# schematic.net
KiCad netlist of a schematic drawn in EAGLE
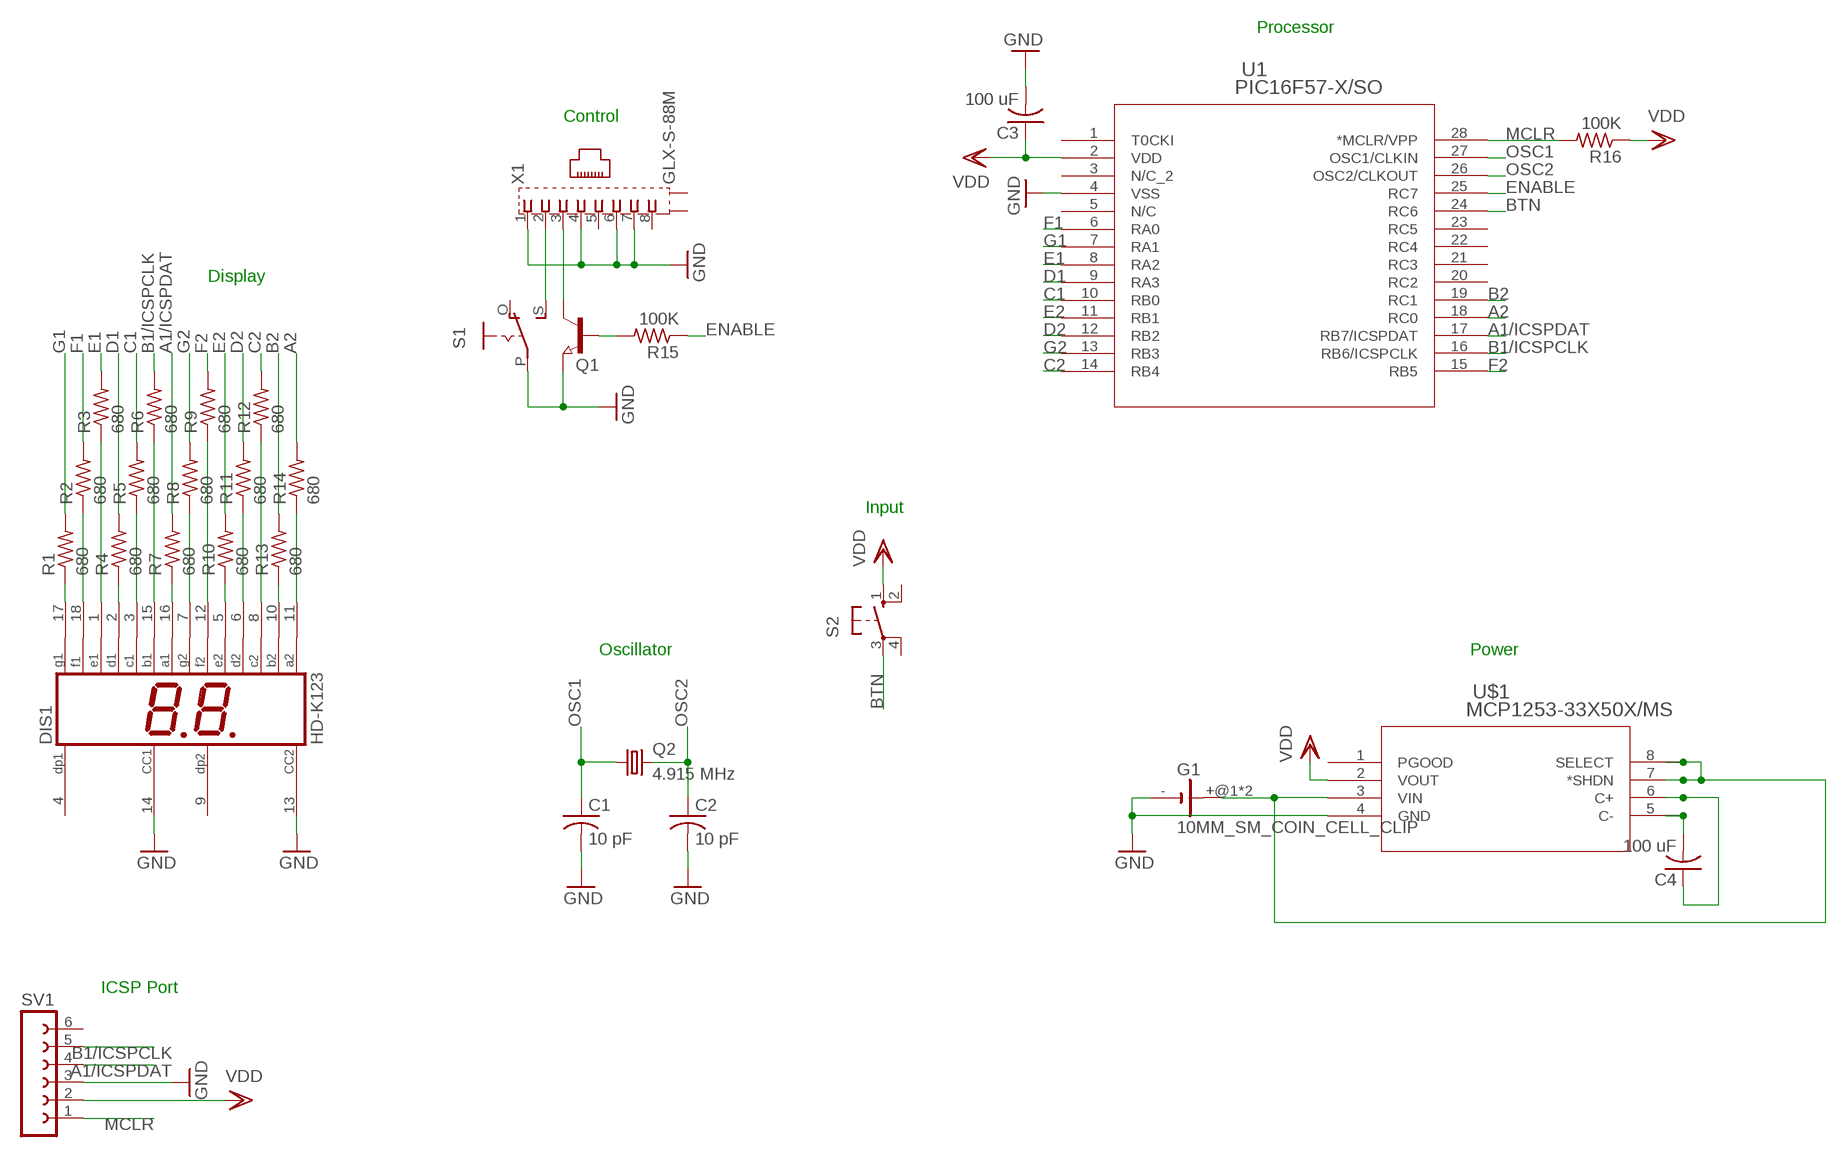
[diagram p0: schematic, sheet 1]

(export (version "E")
  (design (tool "Eeschema 10.0.6"))
  (components
    (comp (ref "C1")
      (value "10 pF")
      (footprint "eagle-import:C0603")
      (libsource (lib "eagle-import") (part "C-USC0603"))
    )
    (comp (ref "C2")
      (value "10 pF")
      (footprint "eagle-import:C0603")
      (libsource (lib "eagle-import") (part "C-USC0603"))
    )
    (comp (ref "C3")
      (value "100 uF")
      (footprint "eagle-import:C0603")
      (libsource (lib "eagle-import") (part "C-USC0603"))
    )
    (comp (ref "C4")
      (value "100 uF")
      (footprint "eagle-import:C0603")
      (libsource (lib "eagle-import") (part "C-USC0603"))
    )
    (comp (ref "DIS1")
      (value "HD-K123")
      (footprint "eagle-import:HDSP-R")
      (libsource (lib "eagle-import") (part "HD-K123"))
    )
    (comp (ref "G1")
      (value "10MM_SM_COIN_CELL_CLIP")
      (footprint "eagle-import:10MM_SM_COIN_CELL_CLIP")
      (libsource (lib "eagle-import") (part "10MM_SM_COIN_CELL_CLIP"))
    )
    (comp (ref "Q1")
      (value "NPN-TRANSISTOR_SOT23")
      (footprint "eagle-import:SOT23")
      (libsource (lib "eagle-import") (part "NPN-TRANSISTOR_SOT23"))
    )
    (comp (ref "Q2")
      (value "4.915 MHz")
      (footprint "eagle-import:SM49")
      (libsource (lib "eagle-import") (part "CRYSTALSM49"))
    )
    (comp (ref "R1")
      (value "680")
      (footprint "eagle-import:R0603")
      (libsource (lib "eagle-import") (part "R-US_R0603"))
    )
    (comp (ref "R2")
      (value "680")
      (footprint "eagle-import:R0603")
      (libsource (lib "eagle-import") (part "R-US_R0603"))
    )
    (comp (ref "R3")
      (value "680")
      (footprint "eagle-import:R0603")
      (libsource (lib "eagle-import") (part "R-US_R0603"))
    )
    (comp (ref "R4")
      (value "680")
      (footprint "eagle-import:R0603")
      (libsource (lib "eagle-import") (part "R-US_R0603"))
    )
    (comp (ref "R5")
      (value "680")
      (footprint "eagle-import:R0603")
      (libsource (lib "eagle-import") (part "R-US_R0603"))
    )
    (comp (ref "R6")
      (value "680")
      (footprint "eagle-import:R0603")
      (libsource (lib "eagle-import") (part "R-US_R0603"))
    )
    (comp (ref "R7")
      (value "680")
      (footprint "eagle-import:R0603")
      (libsource (lib "eagle-import") (part "R-US_R0603"))
    )
    (comp (ref "R8")
      (value "680")
      (footprint "eagle-import:R0603")
      (libsource (lib "eagle-import") (part "R-US_R0603"))
    )
    (comp (ref "R9")
      (value "680")
      (footprint "eagle-import:R0603")
      (libsource (lib "eagle-import") (part "R-US_R0603"))
    )
    (comp (ref "R10")
      (value "680")
      (footprint "eagle-import:R0603")
      (libsource (lib "eagle-import") (part "R-US_R0603"))
    )
    (comp (ref "R11")
      (value "680")
      (footprint "eagle-import:R0603")
      (libsource (lib "eagle-import") (part "R-US_R0603"))
    )
    (comp (ref "R12")
      (value "680")
      (footprint "eagle-import:R0603")
      (libsource (lib "eagle-import") (part "R-US_R0603"))
    )
    (comp (ref "R13")
      (value "680")
      (footprint "eagle-import:R0603")
      (libsource (lib "eagle-import") (part "R-US_R0603"))
    )
    (comp (ref "R14")
      (value "680")
      (footprint "eagle-import:R0603")
      (libsource (lib "eagle-import") (part "R-US_R0603"))
    )
    (comp (ref "R15")
      (value "100K")
      (footprint "eagle-import:R0603")
      (libsource (lib "eagle-import") (part "R-US_R0603"))
    )
    (comp (ref "R16")
      (value "100K")
      (footprint "eagle-import:R0603")
      (libsource (lib "eagle-import") (part "R-US_R0603"))
    )
    (comp (ref "S1")
      (value "EG1218S")
      (footprint "eagle-import:EG1218")
      (libsource (lib "eagle-import") (part "EG1218S"))
    )
    (comp (ref "S2")
      (value "40-XX")
      (footprint "eagle-import:B3F-40XX")
      (fields (field (name "MF") "OMRON COMPONENTS USA") (field (name "MPN") "B3F-4000"))
      (libsource (lib "eagle-import") (part "40-XX"))
    )
    (comp (ref "SV1")
      (value "FE06-1")
      (footprint "eagle-import:FE06")
      (libsource (lib "eagle-import") (part "FE06-1"))
    )
    (comp (ref "U$1")
      (value "MCP1253-33X50X/MS")
      (footprint "eagle-import:MSOP8_MC")
      (libsource (lib "eagle-import") (part "MCP1253-33X50X/MS"))
    )
    (comp (ref "U1")
      (value "PIC16F57-X/SO")
      (footprint "eagle-import:SOIC28-W_MC")
      (libsource (lib "eagle-import") (part "PIC16F57-X/SO"))
    )
    (comp (ref "X1")
      (value "GLX-S-88M")
      (footprint "eagle-import:GLX-S-88M")
      (libsource (lib "eagle-import") (part "GLX-S-88M"))
    )
  )
  (nets
    (net (code "1") (name "/A1{slash}ICSPDAT") (class "Default")
      (node (ref "R7") (pin "2") (pinfunction "2_2") (pintype "passive"))
      (node (ref "SV1") (pin "4") (pinfunction "4_4") (pintype "passive"))
      (node (ref "U1") (pin "17") (pinfunction "RB7/ICSPDAT_17") (pintype "passive"))
    )
    (net (code "2") (name "/A2") (class "Default")
      (node (ref "R14") (pin "2") (pinfunction "2_2") (pintype "passive"))
      (node (ref "U1") (pin "18") (pinfunction "RC0_18") (pintype "passive"))
    )
    (net (code "3") (name "/B1{slash}ICSPCLK") (class "Default")
      (node (ref "R6") (pin "2") (pinfunction "2_2") (pintype "passive"))
      (node (ref "SV1") (pin "5") (pinfunction "5_5") (pintype "passive"))
      (node (ref "U1") (pin "16") (pinfunction "RB6/ICSPCLK_16") (pintype "passive"))
    )
    (net (code "4") (name "/B2") (class "Default")
      (node (ref "R13") (pin "2") (pinfunction "2_2") (pintype "passive"))
      (node (ref "U1") (pin "19") (pinfunction "RC1_19") (pintype "passive"))
    )
    (net (code "5") (name "/BTN") (class "Default")
      (node (ref "S2") (pin "3") (pinfunction "P_3") (pintype "passive"))
      (node (ref "U1") (pin "24") (pinfunction "RC6_24") (pintype "passive"))
    )
    (net (code "6") (name "/C1") (class "Default")
      (node (ref "R5") (pin "2") (pinfunction "2_2") (pintype "passive"))
      (node (ref "U1") (pin "10") (pinfunction "RB0_10") (pintype "passive"))
    )
    (net (code "7") (name "/C2") (class "Default")
      (node (ref "R12") (pin "2") (pinfunction "2_2") (pintype "passive"))
      (node (ref "U1") (pin "14") (pinfunction "RB4_14") (pintype "passive"))
    )
    (net (code "8") (name "/D1") (class "Default")
      (node (ref "R4") (pin "2") (pinfunction "2_2") (pintype "passive"))
      (node (ref "U1") (pin "9") (pinfunction "RA3_9") (pintype "passive"))
    )
    (net (code "9") (name "/D2") (class "Default")
      (node (ref "R11") (pin "2") (pinfunction "2_2") (pintype "passive"))
      (node (ref "U1") (pin "12") (pinfunction "RB2_12") (pintype "passive"))
    )
    (net (code "10") (name "/E1") (class "Default")
      (node (ref "R3") (pin "2") (pinfunction "2_2") (pintype "passive"))
      (node (ref "U1") (pin "8") (pinfunction "RA2_8") (pintype "passive"))
    )
    (net (code "11") (name "/E2") (class "Default")
      (node (ref "R10") (pin "2") (pinfunction "2_2") (pintype "passive"))
      (node (ref "U1") (pin "11") (pinfunction "RB1_11") (pintype "passive"))
    )
    (net (code "12") (name "/ENABLE") (class "Default")
      (node (ref "R15") (pin "1") (pinfunction "1_1") (pintype "passive"))
      (node (ref "U1") (pin "25") (pinfunction "RC7_25") (pintype "passive"))
    )
    (net (code "13") (name "/F1") (class "Default")
      (node (ref "R2") (pin "2") (pinfunction "2_2") (pintype "passive"))
      (node (ref "U1") (pin "6") (pinfunction "RA0_6") (pintype "passive"))
    )
    (net (code "14") (name "/F2") (class "Default")
      (node (ref "R9") (pin "2") (pinfunction "2_2") (pintype "passive"))
      (node (ref "U1") (pin "15") (pinfunction "RB5_15") (pintype "passive"))
    )
    (net (code "15") (name "/G1") (class "Default")
      (node (ref "R1") (pin "2") (pinfunction "2_2") (pintype "passive"))
      (node (ref "U1") (pin "7") (pinfunction "RA1_7") (pintype "passive"))
    )
    (net (code "16") (name "/G2") (class "Default")
      (node (ref "R8") (pin "2") (pinfunction "2_2") (pintype "passive"))
      (node (ref "U1") (pin "13") (pinfunction "RB3_13") (pintype "passive"))
    )
    (net (code "17") (name "/MCLR") (class "Default")
      (node (ref "R16") (pin "2") (pinfunction "2_2") (pintype "passive"))
      (node (ref "SV1") (pin "1") (pinfunction "1_1") (pintype "passive"))
      (node (ref "U1") (pin "28") (pinfunction "*MCLR/VPP_28") (pintype "passive"))
    )
    (net (code "18") (name "/OSC1") (class "Default")
      (node (ref "C1") (pin "1") (pinfunction "1_1") (pintype "passive"))
      (node (ref "Q2") (pin "1") (pinfunction "1_1") (pintype "passive"))
      (node (ref "U1") (pin "27") (pinfunction "OSC1/CLKIN_27") (pintype "passive"))
    )
    (net (code "19") (name "/OSC2") (class "Default")
      (node (ref "C2") (pin "1") (pinfunction "1_1") (pintype "passive"))
      (node (ref "Q2") (pin "2") (pinfunction "2_2") (pintype "passive"))
      (node (ref "U1") (pin "26") (pinfunction "OSC2/CLKOUT_26") (pintype "passive"))
    )
    (net (code "20") (name "GND") (class "Default")
      (node (ref "C1") (pin "2") (pinfunction "2_2") (pintype "passive"))
      (node (ref "C2") (pin "2") (pinfunction "2_2") (pintype "passive"))
      (node (ref "C3") (pin "2") (pinfunction "2_2") (pintype "passive"))
      (node (ref "DIS1") (pin "13") (pinfunction "CC2_13") (pintype "passive"))
      (node (ref "DIS1") (pin "14") (pinfunction "CC1_14") (pintype "passive"))
      (node (ref "G1") (pin "-") (pinfunction "-_-") (pintype "passive"))
      (node (ref "Q1") (pin "2") (pinfunction "E_2") (pintype "passive"))
      (node (ref "S1") (pin "P") (pinfunction "P_P") (pintype "passive"))
      (node (ref "SV1") (pin "3") (pinfunction "3_3") (pintype "passive"))
      (node (ref "U$1") (pin "4") (pinfunction "GND_4") (pintype "passive"))
      (node (ref "U1") (pin "4") (pinfunction "VSS_4") (pintype "passive"))
      (node (ref "X1") (pin "1") (pinfunction "1_1") (pintype "passive"))
      (node (ref "X1") (pin "4") (pinfunction "4_4") (pintype "passive"))
      (node (ref "X1") (pin "6") (pinfunction "6_6") (pintype "passive"))
      (node (ref "X1") (pin "7") (pinfunction "7_7") (pintype "passive"))
    )
    (net (code "21") (name "Net-(DIS1-A1)") (class "Default")
      (node (ref "DIS1") (pin "16") (pinfunction "A1_16") (pintype "passive"))
      (node (ref "R7") (pin "1") (pinfunction "1_1") (pintype "passive"))
    )
    (net (code "22") (name "Net-(DIS1-A2)") (class "Default")
      (node (ref "DIS1") (pin "11") (pinfunction "A2_11") (pintype "passive"))
      (node (ref "R14") (pin "1") (pinfunction "1_1") (pintype "passive"))
    )
    (net (code "23") (name "Net-(DIS1-B1)") (class "Default")
      (node (ref "DIS1") (pin "15") (pinfunction "B1_15") (pintype "passive"))
      (node (ref "R6") (pin "1") (pinfunction "1_1") (pintype "passive"))
    )
    (net (code "24") (name "Net-(DIS1-B2)") (class "Default")
      (node (ref "DIS1") (pin "10") (pinfunction "B2_10") (pintype "passive"))
      (node (ref "R13") (pin "1") (pinfunction "1_1") (pintype "passive"))
    )
    (net (code "25") (name "Net-(DIS1-C1)") (class "Default")
      (node (ref "DIS1") (pin "3") (pinfunction "C1_3") (pintype "passive"))
      (node (ref "R5") (pin "1") (pinfunction "1_1") (pintype "passive"))
    )
    (net (code "26") (name "Net-(DIS1-C2)") (class "Default")
      (node (ref "DIS1") (pin "8") (pinfunction "C2_8") (pintype "passive"))
      (node (ref "R12") (pin "1") (pinfunction "1_1") (pintype "passive"))
    )
    (net (code "27") (name "Net-(DIS1-D1)") (class "Default")
      (node (ref "DIS1") (pin "2") (pinfunction "D1_2") (pintype "passive"))
      (node (ref "R4") (pin "1") (pinfunction "1_1") (pintype "passive"))
    )
    (net (code "28") (name "Net-(DIS1-D2)") (class "Default")
      (node (ref "DIS1") (pin "6") (pinfunction "D2_6") (pintype "passive"))
      (node (ref "R11") (pin "1") (pinfunction "1_1") (pintype "passive"))
    )
    (net (code "29") (name "Net-(DIS1-E1)") (class "Default")
      (node (ref "DIS1") (pin "1") (pinfunction "E1_1") (pintype "passive"))
      (node (ref "R3") (pin "1") (pinfunction "1_1") (pintype "passive"))
    )
    (net (code "30") (name "Net-(DIS1-E2)") (class "Default")
      (node (ref "DIS1") (pin "5") (pinfunction "E2_5") (pintype "passive"))
      (node (ref "R10") (pin "1") (pinfunction "1_1") (pintype "passive"))
    )
    (net (code "31") (name "Net-(DIS1-F1)") (class "Default")
      (node (ref "DIS1") (pin "18") (pinfunction "F1_18") (pintype "passive"))
      (node (ref "R2") (pin "1") (pinfunction "1_1") (pintype "passive"))
    )
    (net (code "32") (name "Net-(DIS1-F2)") (class "Default")
      (node (ref "DIS1") (pin "12") (pinfunction "F2_12") (pintype "passive"))
      (node (ref "R9") (pin "1") (pinfunction "1_1") (pintype "passive"))
    )
    (net (code "33") (name "Net-(DIS1-G1)") (class "Default")
      (node (ref "DIS1") (pin "17") (pinfunction "G1_17") (pintype "passive"))
      (node (ref "R1") (pin "1") (pinfunction "1_1") (pintype "passive"))
    )
    (net (code "34") (name "Net-(DIS1-G2)") (class "Default")
      (node (ref "DIS1") (pin "7") (pinfunction "G2_7") (pintype "passive"))
      (node (ref "R8") (pin "1") (pinfunction "1_1") (pintype "passive"))
    )
    (net (code "35") (name "Net-(Q1-B)") (class "Default")
      (node (ref "Q1") (pin "1") (pinfunction "B_1") (pintype "passive"))
      (node (ref "R15") (pin "2") (pinfunction "2_2") (pintype "passive"))
    )
    (net (code "36") (name "Net-(Q1-C)") (class "Default")
      (node (ref "Q1") (pin "3") (pinfunction "C_3") (pintype "passive"))
      (node (ref "X1") (pin "3") (pinfunction "3_3") (pintype "passive"))
    )
    (net (code "37") (name "Net-(S1-PadS)") (class "Default")
      (node (ref "S1") (pin "S") (pinfunction "S_S") (pintype "passive"))
      (node (ref "X1") (pin "2") (pinfunction "2_2") (pintype "passive"))
    )
    (net (code "38") (name "Net-(U$1-*SHDN)") (class "Default")
      (node (ref "G1") (pin "+@1") (pinfunction "+_+@1") (pintype "passive"))
      (node (ref "G1") (pin "+@2") (pinfunction "+_+@2") (pintype "passive"))
      (node (ref "U$1") (pin "3") (pinfunction "VIN_3") (pintype "passive"))
      (node (ref "U$1") (pin "7") (pinfunction "*SHDN_7") (pintype "passive"))
      (node (ref "U$1") (pin "8") (pinfunction "SELECT_8") (pintype "passive"))
    )
    (net (code "39") (name "Net-(U$1-C+)") (class "Default")
      (node (ref "C4") (pin "1") (pinfunction "1_1") (pintype "passive"))
      (node (ref "U$1") (pin "6") (pinfunction "C+_6") (pintype "passive"))
    )
    (net (code "40") (name "Net-(U$1-C-)") (class "Default")
      (node (ref "C4") (pin "2") (pinfunction "2_2") (pintype "passive"))
      (node (ref "U$1") (pin "5") (pinfunction "C-_5") (pintype "passive"))
    )
    (net (code "41") (name "VDD") (class "Default")
      (node (ref "C3") (pin "1") (pinfunction "1_1") (pintype "passive"))
      (node (ref "R16") (pin "1") (pinfunction "1_1") (pintype "passive"))
      (node (ref "S2") (pin "1") (pinfunction "S_1") (pintype "passive"))
      (node (ref "SV1") (pin "2") (pinfunction "2_2") (pintype "passive"))
      (node (ref "U$1") (pin "2") (pinfunction "VOUT_2") (pintype "passive"))
      (node (ref "U1") (pin "2") (pinfunction "VDD_2") (pintype "passive"))
    )
    (net (code "42") (name "unconnected-(DIS1-DP1-Pad4)") (class "Default")
      (node (ref "DIS1") (pin "4") (pinfunction "DP1_4") (pintype "passive"))
    )
    (net (code "43") (name "unconnected-(DIS1-DP2-Pad9)") (class "Default")
      (node (ref "DIS1") (pin "9") (pinfunction "DP2_9") (pintype "passive"))
    )
    (net (code "44") (name "unconnected-(S1-PadO)") (class "Default")
      (node (ref "S1") (pin "O") (pinfunction "O_O") (pintype "passive"))
    )
    (net (code "45") (name "unconnected-(S2-P1-Pad4)") (class "Default")
      (node (ref "S2") (pin "4") (pinfunction "P1_4") (pintype "passive"))
    )
    (net (code "46") (name "unconnected-(S2-S1-Pad2)") (class "Default")
      (node (ref "S2") (pin "2") (pinfunction "S1_2") (pintype "passive"))
    )
    (net (code "47") (name "unconnected-(SV1-Pad6)") (class "Default")
      (node (ref "SV1") (pin "6") (pinfunction "6_6") (pintype "passive"))
    )
    (net (code "48") (name "unconnected-(U$1-PGOOD-Pad1)") (class "Default")
      (node (ref "U$1") (pin "1") (pinfunction "PGOOD_1") (pintype "passive"))
    )
    (net (code "49") (name "unconnected-(U1-N{slash}C-Pad5)") (class "Default")
      (node (ref "U1") (pin "5") (pinfunction "N/C_5") (pintype "passive"))
    )
    (net (code "50") (name "unconnected-(U1-N{slash}C_2-Pad3)") (class "Default")
      (node (ref "U1") (pin "3") (pinfunction "N/C_2_3") (pintype "passive"))
    )
    (net (code "51") (name "unconnected-(U1-RC2-Pad20)") (class "Default")
      (node (ref "U1") (pin "20") (pinfunction "RC2_20") (pintype "passive"))
    )
    (net (code "52") (name "unconnected-(U1-RC3-Pad21)") (class "Default")
      (node (ref "U1") (pin "21") (pinfunction "RC3_21") (pintype "passive"))
    )
    (net (code "53") (name "unconnected-(U1-RC4-Pad22)") (class "Default")
      (node (ref "U1") (pin "22") (pinfunction "RC4_22") (pintype "passive"))
    )
    (net (code "54") (name "unconnected-(U1-RC5-Pad23)") (class "Default")
      (node (ref "U1") (pin "23") (pinfunction "RC5_23") (pintype "passive"))
    )
    (net (code "55") (name "unconnected-(U1-T0CKI-Pad1)") (class "Default")
      (node (ref "U1") (pin "1") (pinfunction "T0CKI_1") (pintype "passive"))
    )
    (net (code "56") (name "unconnected-(X1-Pad5)") (class "Default")
      (node (ref "X1") (pin "5") (pinfunction "5_5") (pintype "passive"))
    )
    (net (code "57") (name "unconnected-(X1-Pad8)") (class "Default")
      (node (ref "X1") (pin "8") (pinfunction "8_8") (pintype "passive"))
    )
    (net (code "58") (name "unconnected-(X1-PadS1)") (class "Default")
      (node (ref "X1") (pin "S1") (pinfunction "S1_S1") (pintype "passive"))
    )
    (net (code "59") (name "unconnected-(X1-PadS2)") (class "Default")
      (node (ref "X1") (pin "S2") (pinfunction "S2_S2") (pintype "passive"))
    )
  )
)
